# Sheet1.net
KiCad netlist of a schematic drawn in Altium Designer
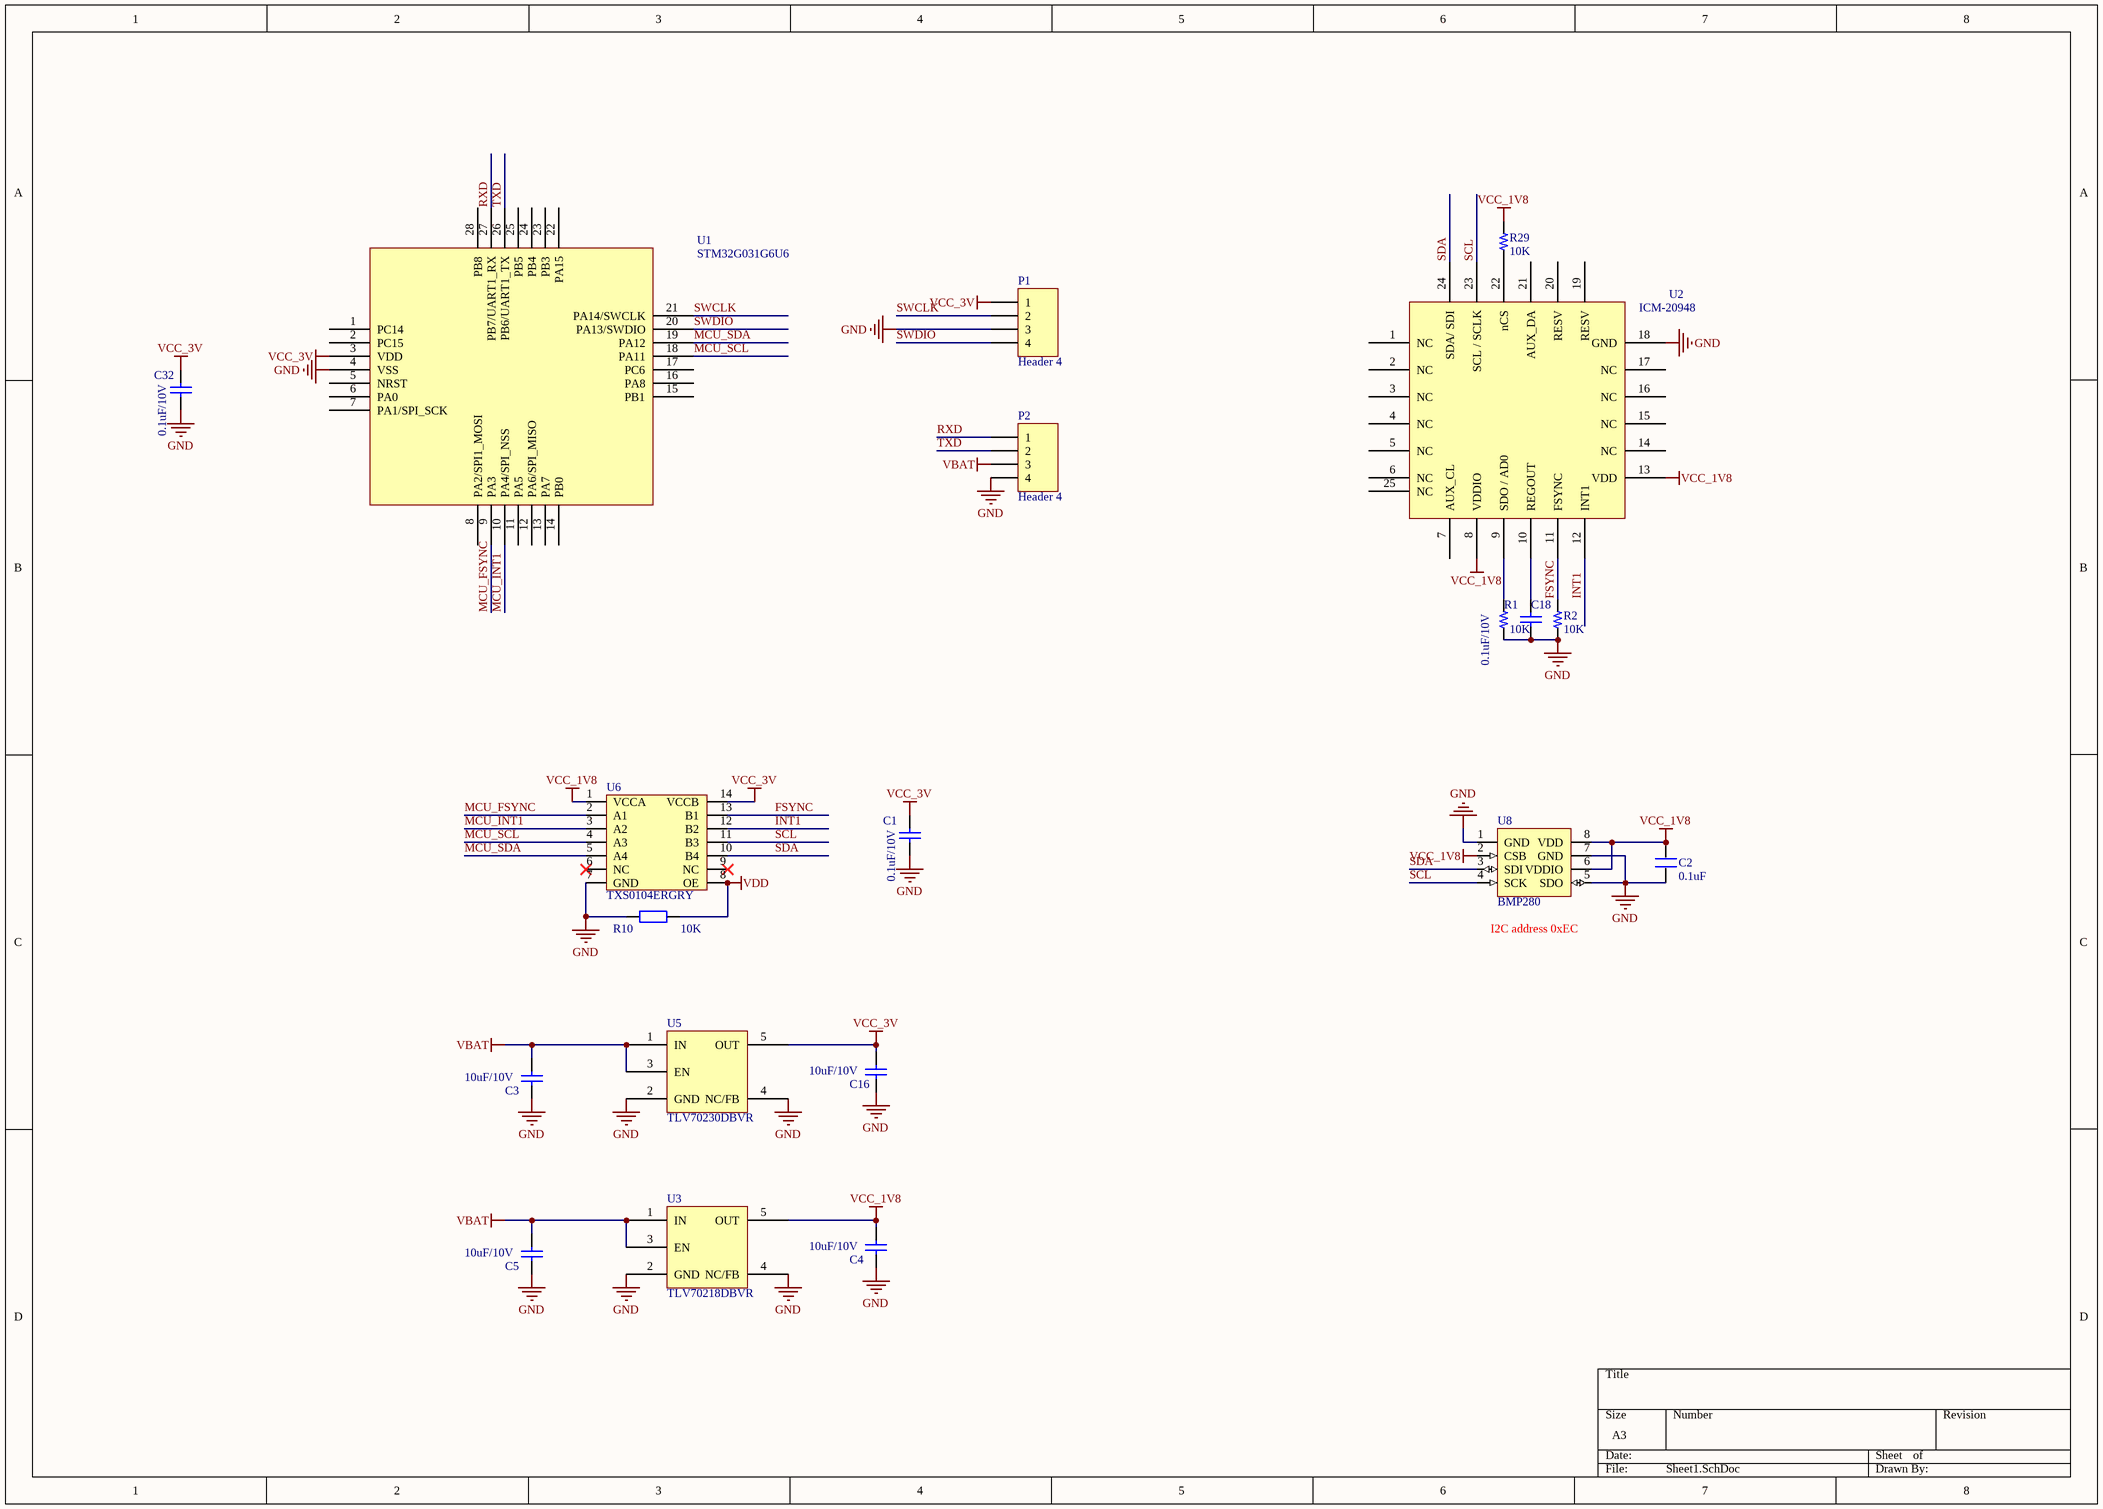
[diagram p0: Sheet1.SchDoc]

(export (version "E")
  (design (tool "Eeschema 10.0.6"))
  (components
    (comp (ref "C1")
      (value "0.1uF/10V")
      (footprint "0402C")
      (description "Capacitor")
      (fields (field (name "PUBLISHER") "Altium Limited"))
      (libsource (lib "Miscellaneous Devices") (part "Cap"))
    )
    (comp (ref "C2") (value "0.1uF") (footprint "0402C") (libsource (lib "MiniFly ") (part "C")))
    (comp (ref "C3")
      (value "10uF/10V")
      (footprint "0603C")
      (description "Capacitor")
      (fields (field (name "PUBLISHER") "Altium Limited"))
      (libsource (lib "Miscellaneous Devices") (part "Cap"))
    )
    (comp (ref "C4")
      (value "10uF/10V")
      (footprint "0603C")
      (description "Capacitor")
      (fields (field (name "PUBLISHER") "Altium Limited"))
      (libsource (lib "Miscellaneous Devices") (part "Cap"))
    )
    (comp (ref "C5")
      (value "10uF/10V")
      (footprint "0603C")
      (description "Capacitor")
      (fields (field (name "PUBLISHER") "Altium Limited"))
      (libsource (lib "Miscellaneous Devices") (part "Cap"))
    )
    (comp (ref "C16")
      (value "10uF/10V")
      (footprint "0603C")
      (description "Capacitor")
      (fields (field (name "PUBLISHER") "Altium Limited"))
      (libsource (lib "Miscellaneous Devices") (part "Cap"))
    )
    (comp (ref "C18")
      (value "0.1uF/10V")
      (footprint "0402C")
      (description "Capacitor")
      (fields (field (name "PUBLISHER") "Altium Limited"))
      (libsource (lib "Miscellaneous Devices") (part "Cap"))
    )
    (comp (ref "C32")
      (value "0.1uF/10V")
      (footprint "0402C")
      (description "Capacitor")
      (fields (field (name "PUBLISHER") "Altium Limited"))
      (libsource (lib "Miscellaneous Devices") (part "Cap"))
    )
    (comp (ref "P1")
      (value "Header 4")
      (footprint "HDR1X4")
      (description "Header, 4-Pin")
      (fields (field (name "PUBLISHER") "Altium Limited"))
      (libsource (lib "Miscellaneous Connectors") (part "Header 4"))
    )
    (comp (ref "P2")
      (value "Header 4")
      (footprint "HDR1X4")
      (description "Header, 4-Pin")
      (fields (field (name "PUBLISHER") "Altium Limited"))
      (libsource (lib "Miscellaneous Connectors") (part "Header 4"))
    )
    (comp (ref "R1") (value "10K") (footprint "0402R") (description "R") (libsource (lib "JRJ_1") (part "R")))
    (comp (ref "R2") (value "10K") (footprint "0402R") (description "R") (libsource (lib "JRJ_1") (part "R")))
    (comp (ref "R10")
      (value "10K")
      (footprint "0402R")
      (description "Resistor")
      (fields (field (name "PUBLISHER") "Altium Limited"))
      (libsource (lib "Miscellaneous Devices") (part "Res2"))
    )
    (comp (ref "R29")
      (value "10K")
      (footprint "0402R")
      (description "R")
      (libsource (lib "JRJ_1") (part "R"))
    )
    (comp (ref "U1")
      (value "STM32G031G6U6")
      (footprint "STM32G031G6U6")
      (libsource (lib "Schlib_20110825") (part "STM32G031G6U6"))
    )
    (comp (ref "U2")
      (value "ICM-20948")
      (footprint "Pcblib_20110825:QFN24-0.4")
      (libsource (lib "Schlib_20110825") (part "ICM-20948"))
    )
    (comp (ref "U3")
      (value "TLV70218DBVR")
      (footprint "SOT23-5(DBV)")
      (libsource (lib "Schlib_20110825") (part "TLV70230DBVR"))
    )
    (comp (ref "U5")
      (value "TLV70230DBVR")
      (footprint "SOT23-5(DBV)")
      (libsource (lib "Schlib_20110825") (part "TLV70230DBVR"))
    )
    (comp (ref "U6")
      (value "TXS0104ERGRY")
      (footprint "TXS0104ERGRY")
      (libsource (lib "Myself_1") (part "TXS0104EPWR"))
    )
    (comp (ref "U8")
      (value "BMP280")
      (footprint "Pcblib_20110825:LGA-8")
      (libsource (lib "MiniFly ") (part "BMP280"))
    )
  )
  (nets
    (net (code "1") (name "/FSYNC") (class "Default")
      (node (ref "R2") (pin "2") (pintype "passive"))
      (node (ref "U2") (pin "11") (pinfunction "FSYNC_11") (pintype "passive"))
      (node (ref "U6") (pin "13") (pinfunction "B1_13") (pintype "passive"))
    )
    (net (code "2") (name "/INT1") (class "Default")
      (node (ref "U2") (pin "12") (pinfunction "INT1_12") (pintype "passive"))
      (node (ref "U6") (pin "12") (pinfunction "B2_12") (pintype "passive"))
    )
    (net (code "3") (name "/MCU_FSYNC") (class "Default")
      (node (ref "U1") (pin "9") (pinfunction "PA3_9") (pintype "passive"))
      (node (ref "U6") (pin "2") (pinfunction "A1_2") (pintype "passive"))
    )
    (net (code "4") (name "/MCU_INT1") (class "Default")
      (node (ref "U1") (pin "10") (pinfunction "PA4/SPI_NSS_10") (pintype "passive"))
      (node (ref "U6") (pin "3") (pinfunction "A2_3") (pintype "passive"))
    )
    (net (code "5") (name "/MCU_SCL") (class "Default")
      (node (ref "U1") (pin "18") (pinfunction "PA11_18") (pintype "passive"))
      (node (ref "U6") (pin "4") (pinfunction "A3_4") (pintype "passive"))
    )
    (net (code "6") (name "/MCU_SDA") (class "Default")
      (node (ref "U1") (pin "19") (pinfunction "PA12_19") (pintype "passive"))
      (node (ref "U6") (pin "5") (pinfunction "A4_5") (pintype "passive"))
    )
    (net (code "7") (name "/RXD") (class "Default")
      (node (ref "P2") (pin "1") (pinfunction "1_1") (pintype "passive"))
      (node (ref "U1") (pin "27") (pinfunction "PB7/UART1_RX_27") (pintype "passive"))
    )
    (net (code "8") (name "/SCL") (class "Default")
      (node (ref "U2") (pin "23") (pinfunction "SCL_/_SCLK_23") (pintype "passive"))
      (node (ref "U6") (pin "11") (pinfunction "B3_11") (pintype "passive"))
      (node (ref "U8") (pin "4") (pinfunction "SCK_4") (pintype "input"))
    )
    (net (code "9") (name "/SDA") (class "Default")
      (node (ref "U2") (pin "24") (pinfunction "SDA/_SDI_24") (pintype "passive"))
      (node (ref "U6") (pin "10") (pinfunction "B4_10") (pintype "passive"))
      (node (ref "U8") (pin "3") (pinfunction "SDI_3") (pintype "bidirectional"))
    )
    (net (code "10") (name "/SWCLK") (class "Default")
      (node (ref "P1") (pin "2") (pinfunction "2_2") (pintype "passive"))
      (node (ref "U1") (pin "21") (pinfunction "PA14/SWCLK_21") (pintype "passive"))
    )
    (net (code "11") (name "/SWDIO") (class "Default")
      (node (ref "P1") (pin "4") (pinfunction "4_4") (pintype "passive"))
      (node (ref "U1") (pin "20") (pinfunction "PA13/SWDIO_20") (pintype "passive"))
    )
    (net (code "12") (name "/TXD") (class "Default")
      (node (ref "P2") (pin "2") (pinfunction "2_2") (pintype "passive"))
      (node (ref "U1") (pin "26") (pinfunction "PB6/UART1_TX_26") (pintype "passive"))
    )
    (net (code "13") (name "GND") (class "Default")
      (node (ref "C1") (pin "2") (pinfunction "2_2") (pintype "passive"))
      (node (ref "C16") (pin "1") (pinfunction "1_1") (pintype "passive"))
      (node (ref "C18") (pin "2") (pinfunction "2_2") (pintype "passive"))
      (node (ref "C2") (pin "1") (pintype "passive"))
      (node (ref "C3") (pin "1") (pinfunction "1_1") (pintype "passive"))
      (node (ref "C32") (pin "2") (pinfunction "2_2") (pintype "passive"))
      (node (ref "C4") (pin "1") (pinfunction "1_1") (pintype "passive"))
      (node (ref "C5") (pin "1") (pinfunction "1_1") (pintype "passive"))
      (node (ref "P1") (pin "3") (pinfunction "3_3") (pintype "passive"))
      (node (ref "P2") (pin "4") (pinfunction "4_4") (pintype "passive"))
      (node (ref "R1") (pin "1") (pintype "passive"))
      (node (ref "R10") (pin "1") (pinfunction "1_1") (pintype "passive"))
      (node (ref "R2") (pin "1") (pintype "passive"))
      (node (ref "U1") (pin "4") (pinfunction "VSS_4") (pintype "passive"))
      (node (ref "U2") (pin "18") (pinfunction "GND_18") (pintype "passive"))
      (node (ref "U3") (pin "2") (pinfunction "GND_2") (pintype "passive"))
      (node (ref "U3") (pin "4") (pinfunction "NC/FB_4") (pintype "passive"))
      (node (ref "U5") (pin "2") (pinfunction "GND_2") (pintype "passive"))
      (node (ref "U5") (pin "4") (pinfunction "NC/FB_4") (pintype "passive"))
      (node (ref "U6") (pin "7") (pinfunction "GND_7") (pintype "passive"))
      (node (ref "U8") (pin "1") (pinfunction "GND_1") (pintype "passive"))
      (node (ref "U8") (pin "5") (pinfunction "SDO_5") (pintype "bidirectional"))
      (node (ref "U8") (pin "7") (pinfunction "GND_7") (pintype "power_in"))
    )
    (net (code "14") (name "Net-(U2-REGOUT)") (class "Default")
      (node (ref "C18") (pin "1") (pinfunction "1_1") (pintype "passive"))
      (node (ref "U2") (pin "10") (pinfunction "REGOUT_10") (pintype "passive"))
    )
    (net (code "15") (name "Net-(U2-SDO_{slash}_AD0)") (class "Default")
      (node (ref "R1") (pin "2") (pintype "passive"))
      (node (ref "U2") (pin "9") (pinfunction "SDO_/_AD0_9") (pintype "passive"))
    )
    (net (code "16") (name "Net-(U2-nCS)") (class "Default")
      (node (ref "R29") (pin "1") (pintype "passive"))
      (node (ref "U2") (pin "22") (pinfunction "nCS_22") (pintype "passive"))
    )
    (net (code "17") (name "VBAT") (class "Default")
      (node (ref "C3") (pin "2") (pinfunction "2_2") (pintype "passive"))
      (node (ref "C5") (pin "2") (pinfunction "2_2") (pintype "passive"))
      (node (ref "P2") (pin "3") (pinfunction "3_3") (pintype "passive"))
      (node (ref "U3") (pin "1") (pinfunction "IN_1") (pintype "passive"))
      (node (ref "U3") (pin "3") (pinfunction "EN_3") (pintype "passive"))
      (node (ref "U5") (pin "1") (pinfunction "IN_1") (pintype "passive"))
      (node (ref "U5") (pin "3") (pinfunction "EN_3") (pintype "passive"))
    )
    (net (code "18") (name "VCC_1V8") (class "Default")
      (node (ref "C2") (pin "2") (pintype "passive"))
      (node (ref "C4") (pin "2") (pinfunction "2_2") (pintype "passive"))
      (node (ref "R29") (pin "2") (pintype "passive"))
      (node (ref "U2") (pin "13") (pinfunction "VDD_13") (pintype "passive"))
      (node (ref "U2") (pin "8") (pinfunction "VDDIO_8") (pintype "passive"))
      (node (ref "U3") (pin "5") (pinfunction "OUT_5") (pintype "passive"))
      (node (ref "U6") (pin "1") (pinfunction "VCCA_1") (pintype "passive"))
      (node (ref "U8") (pin "2") (pinfunction "CSB_2") (pintype "input"))
      (node (ref "U8") (pin "6") (pinfunction "VDDIO_6") (pintype "power_in"))
      (node (ref "U8") (pin "8") (pinfunction "VDD_8") (pintype "power_in"))
    )
    (net (code "19") (name "VCC_3V") (class "Default")
      (node (ref "C1") (pin "1") (pinfunction "1_1") (pintype "passive"))
      (node (ref "C16") (pin "2") (pinfunction "2_2") (pintype "passive"))
      (node (ref "C32") (pin "1") (pinfunction "1_1") (pintype "passive"))
      (node (ref "P1") (pin "1") (pinfunction "1_1") (pintype "passive"))
      (node (ref "U1") (pin "3") (pinfunction "VDD_3") (pintype "passive"))
      (node (ref "U5") (pin "5") (pinfunction "OUT_5") (pintype "passive"))
      (node (ref "U6") (pin "14") (pinfunction "VCCB_14") (pintype "passive"))
    )
    (net (code "20") (name "VDD") (class "Default")
      (node (ref "R10") (pin "2") (pinfunction "2_2") (pintype "passive"))
      (node (ref "U6") (pin "8") (pinfunction "OE_8") (pintype "passive"))
    )
    (net (code "21") (name "unconnected-(U1-NRST-Pad5)") (class "Default")
      (node (ref "U1") (pin "5") (pinfunction "NRST_5") (pintype "passive"))
    )
    (net (code "22") (name "unconnected-(U1-PA0-Pad6)") (class "Default")
      (node (ref "U1") (pin "6") (pinfunction "PA0_6") (pintype "passive"))
    )
    (net (code "23") (name "unconnected-(U1-PA1{slash}SPI_SCK-Pad7)") (class "Default")
      (node (ref "U1") (pin "7") (pinfunction "PA1/SPI_SCK_7") (pintype "passive"))
    )
    (net (code "24") (name "unconnected-(U1-PA2{slash}SPI1_MOSI-Pad8)") (class "Default")
      (node (ref "U1") (pin "8") (pinfunction "PA2/SPI1_MOSI_8") (pintype "passive"))
    )
    (net (code "25") (name "unconnected-(U1-PA5-Pad11)") (class "Default")
      (node (ref "U1") (pin "11") (pinfunction "PA5_11") (pintype "passive"))
    )
    (net (code "26") (name "unconnected-(U1-PA6{slash}SPI_MISO-Pad12)") (class "Default")
      (node (ref "U1") (pin "12") (pinfunction "PA6/SPI_MISO_12") (pintype "passive"))
    )
    (net (code "27") (name "unconnected-(U1-PA7-Pad13)") (class "Default")
      (node (ref "U1") (pin "13") (pinfunction "PA7_13") (pintype "passive"))
    )
    (net (code "28") (name "unconnected-(U1-PA8-Pad16)") (class "Default")
      (node (ref "U1") (pin "16") (pinfunction "PA8_16") (pintype "passive"))
    )
    (net (code "29") (name "unconnected-(U1-PA15-Pad22)") (class "Default")
      (node (ref "U1") (pin "22") (pinfunction "PA15_22") (pintype "passive"))
    )
    (net (code "30") (name "unconnected-(U1-PB0-Pad14)") (class "Default")
      (node (ref "U1") (pin "14") (pinfunction "PB0_14") (pintype "passive"))
    )
    (net (code "31") (name "unconnected-(U1-PB1-Pad15)") (class "Default")
      (node (ref "U1") (pin "15") (pinfunction "PB1_15") (pintype "passive"))
    )
    (net (code "32") (name "unconnected-(U1-PB3-Pad23)") (class "Default")
      (node (ref "U1") (pin "23") (pinfunction "PB3_23") (pintype "passive"))
    )
    (net (code "33") (name "unconnected-(U1-PB4-Pad24)") (class "Default")
      (node (ref "U1") (pin "24") (pinfunction "PB4_24") (pintype "passive"))
    )
    (net (code "34") (name "unconnected-(U1-PB5-Pad25)") (class "Default")
      (node (ref "U1") (pin "25") (pinfunction "PB5_25") (pintype "passive"))
    )
    (net (code "35") (name "unconnected-(U1-PB8-Pad28)") (class "Default")
      (node (ref "U1") (pin "28") (pinfunction "PB8_28") (pintype "passive"))
    )
    (net (code "36") (name "unconnected-(U1-PC6-Pad17)") (class "Default")
      (node (ref "U1") (pin "17") (pinfunction "PC6_17") (pintype "passive"))
    )
    (net (code "37") (name "unconnected-(U1-PC14-Pad1)") (class "Default")
      (node (ref "U1") (pin "1") (pinfunction "PC14_1") (pintype "passive"))
    )
    (net (code "38") (name "unconnected-(U1-PC15-Pad2)") (class "Default")
      (node (ref "U1") (pin "2") (pinfunction "PC15_2") (pintype "passive"))
    )
    (net (code "39") (name "unconnected-(U2-AUX_CL-Pad7)") (class "Default")
      (node (ref "U2") (pin "7") (pinfunction "AUX_CL_7") (pintype "passive"))
    )
    (net (code "40") (name "unconnected-(U2-AUX_DA-Pad21)") (class "Default")
      (node (ref "U2") (pin "21") (pinfunction "AUX_DA_21") (pintype "passive"))
    )
    (net (code "41") (name "unconnected-(U2-NC-Pad1)") (class "Default")
      (node (ref "U2") (pin "1") (pinfunction "NC_1") (pintype "passive"))
    )
    (net (code "42") (name "unconnected-(U2-NC-Pad2)") (class "Default")
      (node (ref "U2") (pin "2") (pinfunction "NC_2") (pintype "passive"))
    )
    (net (code "43") (name "unconnected-(U2-NC-Pad3)") (class "Default")
      (node (ref "U2") (pin "3") (pinfunction "NC_3") (pintype "passive"))
    )
    (net (code "44") (name "unconnected-(U2-NC-Pad4)") (class "Default")
      (node (ref "U2") (pin "4") (pinfunction "NC_4") (pintype "passive"))
    )
    (net (code "45") (name "unconnected-(U2-NC-Pad5)") (class "Default")
      (node (ref "U2") (pin "5") (pinfunction "NC_5") (pintype "passive"))
    )
    (net (code "46") (name "unconnected-(U2-NC-Pad6)") (class "Default")
      (node (ref "U2") (pin "6") (pinfunction "NC_6") (pintype "passive"))
    )
    (net (code "47") (name "unconnected-(U2-NC-Pad14)") (class "Default")
      (node (ref "U2") (pin "14") (pinfunction "NC_14") (pintype "passive"))
    )
    (net (code "48") (name "unconnected-(U2-NC-Pad15)") (class "Default")
      (node (ref "U2") (pin "15") (pinfunction "NC_15") (pintype "passive"))
    )
    (net (code "49") (name "unconnected-(U2-NC-Pad16)") (class "Default")
      (node (ref "U2") (pin "16") (pinfunction "NC_16") (pintype "passive"))
    )
    (net (code "50") (name "unconnected-(U2-NC-Pad17)") (class "Default")
      (node (ref "U2") (pin "17") (pinfunction "NC_17") (pintype "passive"))
    )
    (net (code "51") (name "unconnected-(U2-NC-Pad25)") (class "Default")
      (node (ref "U2") (pin "25") (pinfunction "NC_25") (pintype "passive"))
    )
    (net (code "52") (name "unconnected-(U2-RESV-Pad19)") (class "Default")
      (node (ref "U2") (pin "19") (pinfunction "RESV_19") (pintype "passive"))
    )
    (net (code "53") (name "unconnected-(U2-RESV-Pad20)") (class "Default")
      (node (ref "U2") (pin "20") (pinfunction "RESV_20") (pintype "passive"))
    )
    (net (code "54") (name "unconnected-(U6-NC-Pad6)") (class "Default")
      (node (ref "U6") (pin "6") (pinfunction "NC_6") (pintype "passive+no_connect"))
    )
    (net (code "55") (name "unconnected-(U6-NC-Pad9)") (class "Default")
      (node (ref "U6") (pin "9") (pinfunction "NC_9") (pintype "passive+no_connect"))
    )
  )
)
